# PGTN_daisy3_exp_32io.net
KiCad netlist of a schematic drawn in EAGLE
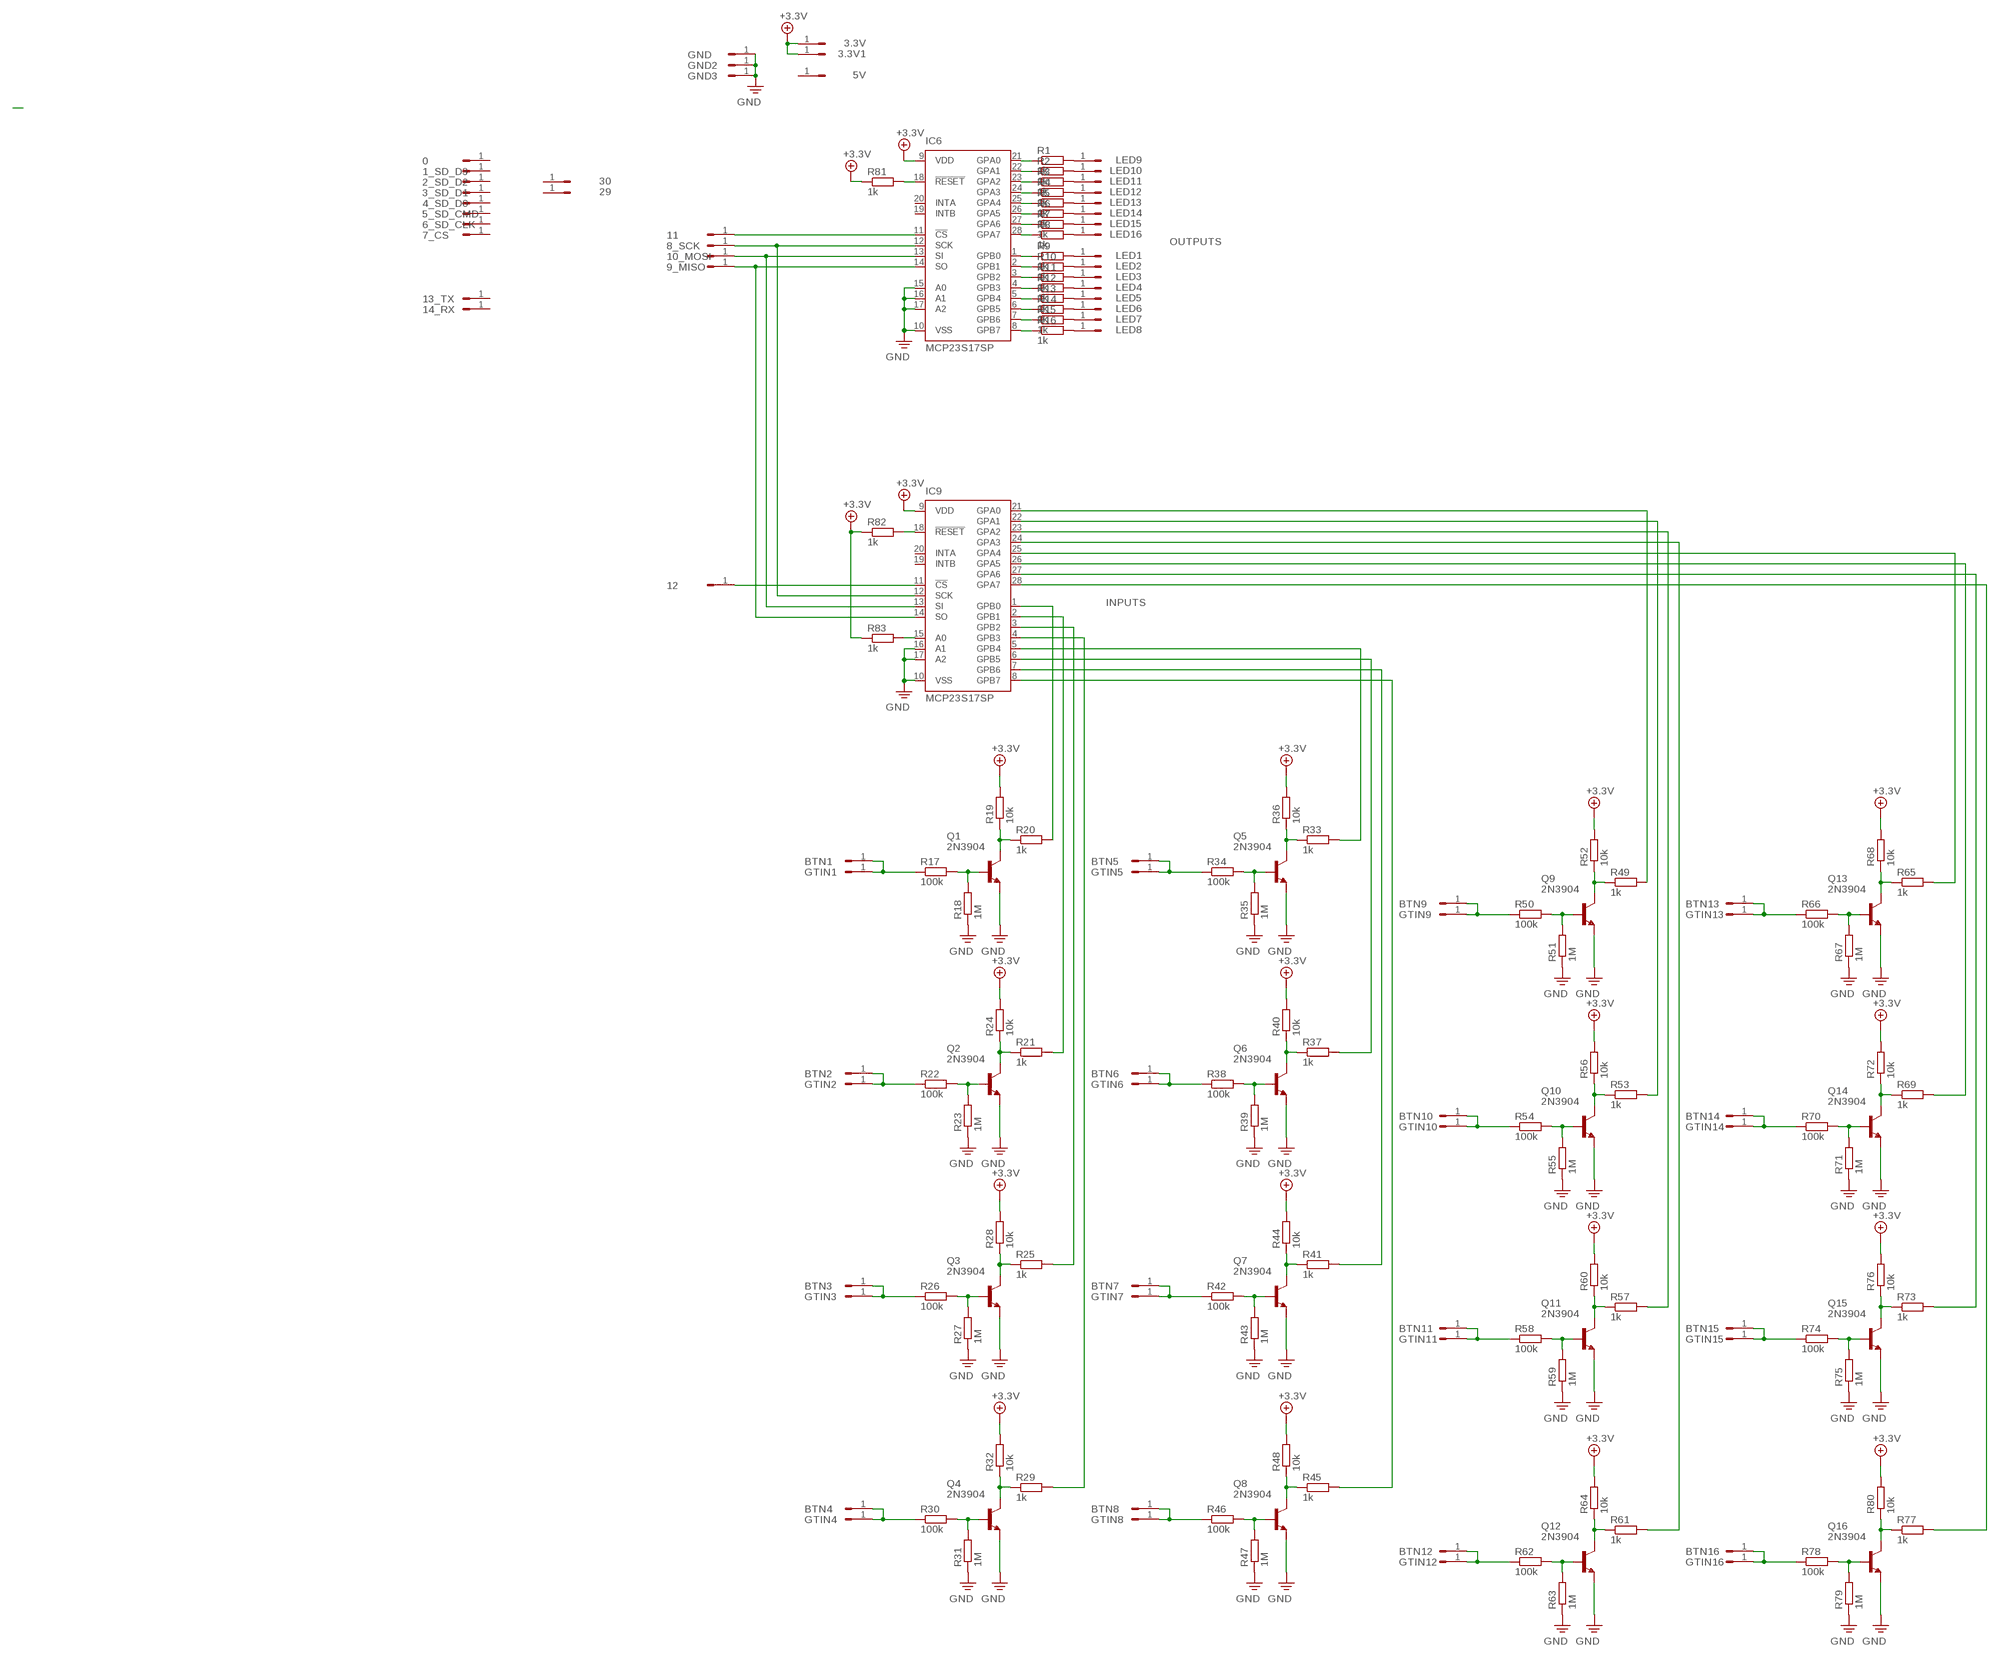
[diagram p0: schematic, sheet 1]

(export (version "E")
  (design (tool "Eeschema 10.0.6"))
  (components
    (comp (ref "0")
      (value "HEADER/MALE/01")
      (footprint "eagle-import:HEADER_MALE_01")
      (fields (field (name "SPICEPREFIX") "X"))
      (libsource (lib "eagle-import") (part "HEADER/MALE/01"))
    )
    (comp (ref "1_SD_D3")
      (value "HEADER/MALE/01")
      (footprint "eagle-import:HEADER_MALE_01")
      (fields (field (name "SPICEPREFIX") "X"))
      (libsource (lib "eagle-import") (part "HEADER/MALE/01"))
    )
    (comp (ref "2_SD_D2")
      (value "HEADER/MALE/01")
      (footprint "eagle-import:HEADER_MALE_01")
      (fields (field (name "SPICEPREFIX") "X"))
      (libsource (lib "eagle-import") (part "HEADER/MALE/01"))
    )
    (comp (ref "3.3V")
      (value "HEADER/MALE/01")
      (footprint "eagle-import:HEADER_MALE_01")
      (fields (field (name "SPICEPREFIX") "X"))
      (libsource (lib "eagle-import") (part "HEADER/MALE/01"))
    )
    (comp (ref "3.3V1")
      (value "HEADER/MALE/01")
      (footprint "eagle-import:HEADER_MALE_01")
      (fields (field (name "SPICEPREFIX") "X"))
      (libsource (lib "eagle-import") (part "HEADER/MALE/01"))
    )
    (comp (ref "3_SD_D1")
      (value "HEADER/MALE/01")
      (footprint "eagle-import:HEADER_MALE_01")
      (fields (field (name "SPICEPREFIX") "X"))
      (libsource (lib "eagle-import") (part "HEADER/MALE/01"))
    )
    (comp (ref "4_SD_D0")
      (value "HEADER/MALE/01")
      (footprint "eagle-import:HEADER_MALE_01")
      (fields (field (name "SPICEPREFIX") "X"))
      (libsource (lib "eagle-import") (part "HEADER/MALE/01"))
    )
    (comp (ref "5V")
      (value "HEADER/MALE/01")
      (footprint "eagle-import:HEADER_MALE_01")
      (fields (field (name "SPICEPREFIX") "X"))
      (libsource (lib "eagle-import") (part "HEADER/MALE/01"))
    )
    (comp (ref "5_SD_CMD")
      (value "HEADER/MALE/01")
      (footprint "eagle-import:HEADER_MALE_01")
      (fields (field (name "SPICEPREFIX") "X"))
      (libsource (lib "eagle-import") (part "HEADER/MALE/01"))
    )
    (comp (ref "6_SD_CLK")
      (value "HEADER/MALE/01")
      (footprint "eagle-import:HEADER_MALE_01")
      (fields (field (name "SPICEPREFIX") "X"))
      (libsource (lib "eagle-import") (part "HEADER/MALE/01"))
    )
    (comp (ref "7_CS")
      (value "HEADER/MALE/01")
      (footprint "eagle-import:HEADER_MALE_01")
      (fields (field (name "SPICEPREFIX") "X"))
      (libsource (lib "eagle-import") (part "HEADER/MALE/01"))
    )
    (comp (ref "8_SCK")
      (value "HEADER/MALE/01")
      (footprint "eagle-import:HEADER_MALE_01")
      (fields (field (name "SPICEPREFIX") "X"))
      (libsource (lib "eagle-import") (part "HEADER/MALE/01"))
    )
    (comp (ref "9_MISO")
      (value "HEADER/MALE/01")
      (footprint "eagle-import:HEADER_MALE_01")
      (fields (field (name "SPICEPREFIX") "X"))
      (libsource (lib "eagle-import") (part "HEADER/MALE/01"))
    )
    (comp (ref "10_MOSI")
      (value "HEADER/MALE/01")
      (footprint "eagle-import:HEADER_MALE_01")
      (fields (field (name "SPICEPREFIX") "X"))
      (libsource (lib "eagle-import") (part "HEADER/MALE/01"))
    )
    (comp (ref "11")
      (value "HEADER/MALE/01")
      (footprint "eagle-import:HEADER_MALE_01")
      (fields (field (name "SPICEPREFIX") "X"))
      (libsource (lib "eagle-import") (part "HEADER/MALE/01"))
    )
    (comp (ref "12")
      (value "HEADER/MALE/01")
      (footprint "eagle-import:HEADER_MALE_01")
      (fields (field (name "SPICEPREFIX") "X"))
      (libsource (lib "eagle-import") (part "HEADER/MALE/01"))
    )
    (comp (ref "13_TX")
      (value "HEADER/MALE/01")
      (footprint "eagle-import:HEADER_MALE_01")
      (fields (field (name "SPICEPREFIX") "X"))
      (libsource (lib "eagle-import") (part "HEADER/MALE/01"))
    )
    (comp (ref "14_RX")
      (value "HEADER/MALE/01")
      (footprint "eagle-import:HEADER_MALE_01")
      (fields (field (name "SPICEPREFIX") "X"))
      (libsource (lib "eagle-import") (part "HEADER/MALE/01"))
    )
    (comp (ref "29")
      (value "HEADER/MALE/01")
      (footprint "eagle-import:HEADER_MALE_01")
      (fields (field (name "SPICEPREFIX") "X"))
      (libsource (lib "eagle-import") (part "HEADER/MALE/01"))
    )
    (comp (ref "30")
      (value "HEADER/MALE/01")
      (footprint "eagle-import:HEADER_MALE_01")
      (fields (field (name "SPICEPREFIX") "X"))
      (libsource (lib "eagle-import") (part "HEADER/MALE/01"))
    )
    (comp (ref "BTN1")
      (value "HEADER/MALE/01")
      (footprint "eagle-import:HEADER_MALE_01")
      (fields (field (name "SPICEPREFIX") "X"))
      (libsource (lib "eagle-import") (part "HEADER/MALE/01"))
    )
    (comp (ref "BTN2")
      (value "HEADER/MALE/01")
      (footprint "eagle-import:HEADER_MALE_01")
      (fields (field (name "SPICEPREFIX") "X"))
      (libsource (lib "eagle-import") (part "HEADER/MALE/01"))
    )
    (comp (ref "BTN3")
      (value "HEADER/MALE/01")
      (footprint "eagle-import:HEADER_MALE_01")
      (fields (field (name "SPICEPREFIX") "X"))
      (libsource (lib "eagle-import") (part "HEADER/MALE/01"))
    )
    (comp (ref "BTN4")
      (value "HEADER/MALE/01")
      (footprint "eagle-import:HEADER_MALE_01")
      (fields (field (name "SPICEPREFIX") "X"))
      (libsource (lib "eagle-import") (part "HEADER/MALE/01"))
    )
    (comp (ref "BTN5")
      (value "HEADER/MALE/01")
      (footprint "eagle-import:HEADER_MALE_01")
      (fields (field (name "SPICEPREFIX") "X"))
      (libsource (lib "eagle-import") (part "HEADER/MALE/01"))
    )
    (comp (ref "BTN6")
      (value "HEADER/MALE/01")
      (footprint "eagle-import:HEADER_MALE_01")
      (fields (field (name "SPICEPREFIX") "X"))
      (libsource (lib "eagle-import") (part "HEADER/MALE/01"))
    )
    (comp (ref "BTN7")
      (value "HEADER/MALE/01")
      (footprint "eagle-import:HEADER_MALE_01")
      (fields (field (name "SPICEPREFIX") "X"))
      (libsource (lib "eagle-import") (part "HEADER/MALE/01"))
    )
    (comp (ref "BTN8")
      (value "HEADER/MALE/01")
      (footprint "eagle-import:HEADER_MALE_01")
      (fields (field (name "SPICEPREFIX") "X"))
      (libsource (lib "eagle-import") (part "HEADER/MALE/01"))
    )
    (comp (ref "BTN9")
      (value "HEADER/MALE/01")
      (footprint "eagle-import:HEADER_MALE_01")
      (fields (field (name "SPICEPREFIX") "X"))
      (libsource (lib "eagle-import") (part "HEADER/MALE/01"))
    )
    (comp (ref "BTN10")
      (value "HEADER/MALE/01")
      (footprint "eagle-import:HEADER_MALE_01")
      (fields (field (name "SPICEPREFIX") "X"))
      (libsource (lib "eagle-import") (part "HEADER/MALE/01"))
    )
    (comp (ref "BTN11")
      (value "HEADER/MALE/01")
      (footprint "eagle-import:HEADER_MALE_01")
      (fields (field (name "SPICEPREFIX") "X"))
      (libsource (lib "eagle-import") (part "HEADER/MALE/01"))
    )
    (comp (ref "BTN12")
      (value "HEADER/MALE/01")
      (footprint "eagle-import:HEADER_MALE_01")
      (fields (field (name "SPICEPREFIX") "X"))
      (libsource (lib "eagle-import") (part "HEADER/MALE/01"))
    )
    (comp (ref "BTN13")
      (value "HEADER/MALE/01")
      (footprint "eagle-import:HEADER_MALE_01")
      (fields (field (name "SPICEPREFIX") "X"))
      (libsource (lib "eagle-import") (part "HEADER/MALE/01"))
    )
    (comp (ref "BTN14")
      (value "HEADER/MALE/01")
      (footprint "eagle-import:HEADER_MALE_01")
      (fields (field (name "SPICEPREFIX") "X"))
      (libsource (lib "eagle-import") (part "HEADER/MALE/01"))
    )
    (comp (ref "BTN15")
      (value "HEADER/MALE/01")
      (footprint "eagle-import:HEADER_MALE_01")
      (fields (field (name "SPICEPREFIX") "X"))
      (libsource (lib "eagle-import") (part "HEADER/MALE/01"))
    )
    (comp (ref "BTN16")
      (value "HEADER/MALE/01")
      (footprint "eagle-import:HEADER_MALE_01")
      (fields (field (name "SPICEPREFIX") "X"))
      (libsource (lib "eagle-import") (part "HEADER/MALE/01"))
    )
    (comp (ref "GND")
      (value "HEADER/MALE/01")
      (footprint "eagle-import:HEADER_MALE_01")
      (fields (field (name "SPICEPREFIX") "X"))
      (libsource (lib "eagle-import") (part "HEADER/MALE/01"))
    )
    (comp (ref "GND2")
      (value "HEADER/MALE/01")
      (footprint "eagle-import:HEADER_MALE_01")
      (fields (field (name "SPICEPREFIX") "X"))
      (libsource (lib "eagle-import") (part "HEADER/MALE/01"))
    )
    (comp (ref "GND3")
      (value "HEADER/MALE/01")
      (footprint "eagle-import:HEADER_MALE_01")
      (fields (field (name "SPICEPREFIX") "X"))
      (libsource (lib "eagle-import") (part "HEADER/MALE/01"))
    )
    (comp (ref "GTIN1")
      (value "HEADER/MALE/01")
      (footprint "eagle-import:HEADER_MALE_01")
      (fields (field (name "SPICEPREFIX") "X"))
      (libsource (lib "eagle-import") (part "HEADER/MALE/01"))
    )
    (comp (ref "GTIN2")
      (value "HEADER/MALE/01")
      (footprint "eagle-import:HEADER_MALE_01")
      (fields (field (name "SPICEPREFIX") "X"))
      (libsource (lib "eagle-import") (part "HEADER/MALE/01"))
    )
    (comp (ref "GTIN3")
      (value "HEADER/MALE/01")
      (footprint "eagle-import:HEADER_MALE_01")
      (fields (field (name "SPICEPREFIX") "X"))
      (libsource (lib "eagle-import") (part "HEADER/MALE/01"))
    )
    (comp (ref "GTIN4")
      (value "HEADER/MALE/01")
      (footprint "eagle-import:HEADER_MALE_01")
      (fields (field (name "SPICEPREFIX") "X"))
      (libsource (lib "eagle-import") (part "HEADER/MALE/01"))
    )
    (comp (ref "GTIN5")
      (value "HEADER/MALE/01")
      (footprint "eagle-import:HEADER_MALE_01")
      (fields (field (name "SPICEPREFIX") "X"))
      (libsource (lib "eagle-import") (part "HEADER/MALE/01"))
    )
    (comp (ref "GTIN6")
      (value "HEADER/MALE/01")
      (footprint "eagle-import:HEADER_MALE_01")
      (fields (field (name "SPICEPREFIX") "X"))
      (libsource (lib "eagle-import") (part "HEADER/MALE/01"))
    )
    (comp (ref "GTIN7")
      (value "HEADER/MALE/01")
      (footprint "eagle-import:HEADER_MALE_01")
      (fields (field (name "SPICEPREFIX") "X"))
      (libsource (lib "eagle-import") (part "HEADER/MALE/01"))
    )
    (comp (ref "GTIN8")
      (value "HEADER/MALE/01")
      (footprint "eagle-import:HEADER_MALE_01")
      (fields (field (name "SPICEPREFIX") "X"))
      (libsource (lib "eagle-import") (part "HEADER/MALE/01"))
    )
    (comp (ref "GTIN9")
      (value "HEADER/MALE/01")
      (footprint "eagle-import:HEADER_MALE_01")
      (fields (field (name "SPICEPREFIX") "X"))
      (libsource (lib "eagle-import") (part "HEADER/MALE/01"))
    )
    (comp (ref "GTIN10")
      (value "HEADER/MALE/01")
      (footprint "eagle-import:HEADER_MALE_01")
      (fields (field (name "SPICEPREFIX") "X"))
      (libsource (lib "eagle-import") (part "HEADER/MALE/01"))
    )
    (comp (ref "GTIN11")
      (value "HEADER/MALE/01")
      (footprint "eagle-import:HEADER_MALE_01")
      (fields (field (name "SPICEPREFIX") "X"))
      (libsource (lib "eagle-import") (part "HEADER/MALE/01"))
    )
    (comp (ref "GTIN12")
      (value "HEADER/MALE/01")
      (footprint "eagle-import:HEADER_MALE_01")
      (fields (field (name "SPICEPREFIX") "X"))
      (libsource (lib "eagle-import") (part "HEADER/MALE/01"))
    )
    (comp (ref "GTIN13")
      (value "HEADER/MALE/01")
      (footprint "eagle-import:HEADER_MALE_01")
      (fields (field (name "SPICEPREFIX") "X"))
      (libsource (lib "eagle-import") (part "HEADER/MALE/01"))
    )
    (comp (ref "GTIN14")
      (value "HEADER/MALE/01")
      (footprint "eagle-import:HEADER_MALE_01")
      (fields (field (name "SPICEPREFIX") "X"))
      (libsource (lib "eagle-import") (part "HEADER/MALE/01"))
    )
    (comp (ref "GTIN15")
      (value "HEADER/MALE/01")
      (footprint "eagle-import:HEADER_MALE_01")
      (fields (field (name "SPICEPREFIX") "X"))
      (libsource (lib "eagle-import") (part "HEADER/MALE/01"))
    )
    (comp (ref "GTIN16")
      (value "HEADER/MALE/01")
      (footprint "eagle-import:HEADER_MALE_01")
      (fields (field (name "SPICEPREFIX") "X"))
      (libsource (lib "eagle-import") (part "HEADER/MALE/01"))
    )
    (comp (ref "IC6")
      (value "MCP23S17SP")
      (footprint "eagle-import:DIL28-3")
      (fields (field (name "MF") "MICROCHIP") (field (name "MPN") "MCP23S17-E/SP"))
      (libsource (lib "eagle-import") (part "MCP23S17SP"))
    )
    (comp (ref "IC9")
      (value "MCP23S17SP")
      (footprint "eagle-import:DIL28-3")
      (fields (field (name "MF") "MICROCHIP") (field (name "MPN") "MCP23S17-E/SP"))
      (libsource (lib "eagle-import") (part "MCP23S17SP"))
    )
    (comp (ref "LED1")
      (value "HEADER/MALE/01")
      (footprint "eagle-import:HEADER_MALE_01")
      (fields (field (name "SPICEPREFIX") "X"))
      (libsource (lib "eagle-import") (part "HEADER/MALE/01"))
    )
    (comp (ref "LED2")
      (value "HEADER/MALE/01")
      (footprint "eagle-import:HEADER_MALE_01")
      (fields (field (name "SPICEPREFIX") "X"))
      (libsource (lib "eagle-import") (part "HEADER/MALE/01"))
    )
    (comp (ref "LED3")
      (value "HEADER/MALE/01")
      (footprint "eagle-import:HEADER_MALE_01")
      (fields (field (name "SPICEPREFIX") "X"))
      (libsource (lib "eagle-import") (part "HEADER/MALE/01"))
    )
    (comp (ref "LED4")
      (value "HEADER/MALE/01")
      (footprint "eagle-import:HEADER_MALE_01")
      (fields (field (name "SPICEPREFIX") "X"))
      (libsource (lib "eagle-import") (part "HEADER/MALE/01"))
    )
    (comp (ref "LED5")
      (value "HEADER/MALE/01")
      (footprint "eagle-import:HEADER_MALE_01")
      (fields (field (name "SPICEPREFIX") "X"))
      (libsource (lib "eagle-import") (part "HEADER/MALE/01"))
    )
    (comp (ref "LED6")
      (value "HEADER/MALE/01")
      (footprint "eagle-import:HEADER_MALE_01")
      (fields (field (name "SPICEPREFIX") "X"))
      (libsource (lib "eagle-import") (part "HEADER/MALE/01"))
    )
    (comp (ref "LED7")
      (value "HEADER/MALE/01")
      (footprint "eagle-import:HEADER_MALE_01")
      (fields (field (name "SPICEPREFIX") "X"))
      (libsource (lib "eagle-import") (part "HEADER/MALE/01"))
    )
    (comp (ref "LED8")
      (value "HEADER/MALE/01")
      (footprint "eagle-import:HEADER_MALE_01")
      (fields (field (name "SPICEPREFIX") "X"))
      (libsource (lib "eagle-import") (part "HEADER/MALE/01"))
    )
    (comp (ref "LED9")
      (value "HEADER/MALE/01")
      (footprint "eagle-import:HEADER_MALE_01")
      (fields (field (name "SPICEPREFIX") "X"))
      (libsource (lib "eagle-import") (part "HEADER/MALE/01"))
    )
    (comp (ref "LED10")
      (value "HEADER/MALE/01")
      (footprint "eagle-import:HEADER_MALE_01")
      (fields (field (name "SPICEPREFIX") "X"))
      (libsource (lib "eagle-import") (part "HEADER/MALE/01"))
    )
    (comp (ref "LED11")
      (value "HEADER/MALE/01")
      (footprint "eagle-import:HEADER_MALE_01")
      (fields (field (name "SPICEPREFIX") "X"))
      (libsource (lib "eagle-import") (part "HEADER/MALE/01"))
    )
    (comp (ref "LED12")
      (value "HEADER/MALE/01")
      (footprint "eagle-import:HEADER_MALE_01")
      (fields (field (name "SPICEPREFIX") "X"))
      (libsource (lib "eagle-import") (part "HEADER/MALE/01"))
    )
    (comp (ref "LED13")
      (value "HEADER/MALE/01")
      (footprint "eagle-import:HEADER_MALE_01")
      (fields (field (name "SPICEPREFIX") "X"))
      (libsource (lib "eagle-import") (part "HEADER/MALE/01"))
    )
    (comp (ref "LED14")
      (value "HEADER/MALE/01")
      (footprint "eagle-import:HEADER_MALE_01")
      (fields (field (name "SPICEPREFIX") "X"))
      (libsource (lib "eagle-import") (part "HEADER/MALE/01"))
    )
    (comp (ref "LED15")
      (value "HEADER/MALE/01")
      (footprint "eagle-import:HEADER_MALE_01")
      (fields (field (name "SPICEPREFIX") "X"))
      (libsource (lib "eagle-import") (part "HEADER/MALE/01"))
    )
    (comp (ref "LED16")
      (value "HEADER/MALE/01")
      (footprint "eagle-import:HEADER_MALE_01")
      (fields (field (name "SPICEPREFIX") "X"))
      (libsource (lib "eagle-import") (part "HEADER/MALE/01"))
    )
    (comp (ref "Q1")
      (value "2N3904")
      (footprint "eagle-import:TO92")
      (libsource (lib "eagle-import") (part "2N3904"))
    )
    (comp (ref "Q2")
      (value "2N3904")
      (footprint "eagle-import:TO92")
      (libsource (lib "eagle-import") (part "2N3904"))
    )
    (comp (ref "Q3")
      (value "2N3904")
      (footprint "eagle-import:TO92")
      (libsource (lib "eagle-import") (part "2N3904"))
    )
    (comp (ref "Q4")
      (value "2N3904")
      (footprint "eagle-import:TO92")
      (libsource (lib "eagle-import") (part "2N3904"))
    )
    (comp (ref "Q5")
      (value "2N3904")
      (footprint "eagle-import:TO92")
      (libsource (lib "eagle-import") (part "2N3904"))
    )
    (comp (ref "Q6")
      (value "2N3904")
      (footprint "eagle-import:TO92")
      (libsource (lib "eagle-import") (part "2N3904"))
    )
    (comp (ref "Q7")
      (value "2N3904")
      (footprint "eagle-import:TO92")
      (libsource (lib "eagle-import") (part "2N3904"))
    )
    (comp (ref "Q8")
      (value "2N3904")
      (footprint "eagle-import:TO92")
      (libsource (lib "eagle-import") (part "2N3904"))
    )
    (comp (ref "Q9")
      (value "2N3904")
      (footprint "eagle-import:TO92")
      (libsource (lib "eagle-import") (part "2N3904"))
    )
    (comp (ref "Q10")
      (value "2N3904")
      (footprint "eagle-import:TO92")
      (libsource (lib "eagle-import") (part "2N3904"))
    )
    (comp (ref "Q11")
      (value "2N3904")
      (footprint "eagle-import:TO92")
      (libsource (lib "eagle-import") (part "2N3904"))
    )
    (comp (ref "Q12")
      (value "2N3904")
      (footprint "eagle-import:TO92")
      (libsource (lib "eagle-import") (part "2N3904"))
    )
    (comp (ref "Q13")
      (value "2N3904")
      (footprint "eagle-import:TO92")
      (libsource (lib "eagle-import") (part "2N3904"))
    )
    (comp (ref "Q14")
      (value "2N3904")
      (footprint "eagle-import:TO92")
      (libsource (lib "eagle-import") (part "2N3904"))
    )
    (comp (ref "Q15")
      (value "2N3904")
      (footprint "eagle-import:TO92")
      (libsource (lib "eagle-import") (part "2N3904"))
    )
    (comp (ref "Q16")
      (value "2N3904")
      (footprint "eagle-import:TO92")
      (libsource (lib "eagle-import") (part "2N3904"))
    )
    (comp (ref "R1")
      (value "1k")
      (footprint "eagle-import:RESISTOR_7.5")
      (libsource (lib "eagle-import") (part "RESISTORRESISTOR/UPRIGHT/7.5"))
    )
    (comp (ref "R2")
      (value "1k")
      (footprint "eagle-import:RESISTOR_7.5")
      (libsource (lib "eagle-import") (part "RESISTORRESISTOR/UPRIGHT/7.5"))
    )
    (comp (ref "R3")
      (value "1k")
      (footprint "eagle-import:RESISTOR_7.5")
      (libsource (lib "eagle-import") (part "RESISTORRESISTOR/UPRIGHT/7.5"))
    )
    (comp (ref "R4")
      (value "1k")
      (footprint "eagle-import:RESISTOR_7.5")
      (libsource (lib "eagle-import") (part "RESISTORRESISTOR/UPRIGHT/7.5"))
    )
    (comp (ref "R5")
      (value "1k")
      (footprint "eagle-import:RESISTOR_7.5")
      (libsource (lib "eagle-import") (part "RESISTORRESISTOR/UPRIGHT/7.5"))
    )
    (comp (ref "R6")
      (value "1k")
      (footprint "eagle-import:RESISTOR_7.5")
      (libsource (lib "eagle-import") (part "RESISTORRESISTOR/UPRIGHT/7.5"))
    )
    (comp (ref "R7")
      (value "1k")
      (footprint "eagle-import:RESISTOR_7.5")
      (libsource (lib "eagle-import") (part "RESISTORRESISTOR/UPRIGHT/7.5"))
    )
    (comp (ref "R8")
      (value "1k")
      (footprint "eagle-import:RESISTOR_7.5")
      (libsource (lib "eagle-import") (part "RESISTORRESISTOR/UPRIGHT/7.5"))
    )
    (comp (ref "R9")
      (value "1k")
      (footprint "eagle-import:RESISTOR_7.5")
      (libsource (lib "eagle-import") (part "RESISTORRESISTOR/UPRIGHT/7.5"))
    )
    (comp (ref "R10")
      (value "1k")
      (footprint "eagle-import:RESISTOR_7.5")
      (libsource (lib "eagle-import") (part "RESISTORRESISTOR/UPRIGHT/7.5"))
    )
    (comp (ref "R11")
      (value "1k")
      (footprint "eagle-import:RESISTOR_7.5")
      (libsource (lib "eagle-import") (part "RESISTORRESISTOR/UPRIGHT/7.5"))
    )
    (comp (ref "R12")
      (value "1k")
      (footprint "eagle-import:RESISTOR_7.5")
      (libsource (lib "eagle-import") (part "RESISTORRESISTOR/UPRIGHT/7.5"))
    )
    (comp (ref "R13")
      (value "1k")
      (footprint "eagle-import:RESISTOR_7.5")
      (libsource (lib "eagle-import") (part "RESISTORRESISTOR/UPRIGHT/7.5"))
    )
    (comp (ref "R14")
      (value "1k")
      (footprint "eagle-import:RESISTOR_7.5")
      (libsource (lib "eagle-import") (part "RESISTORRESISTOR/UPRIGHT/7.5"))
    )
    (comp (ref "R15")
      (value "1k")
      (footprint "eagle-import:RESISTOR_7.5")
      (libsource (lib "eagle-import") (part "RESISTORRESISTOR/UPRIGHT/7.5"))
    )
    (comp (ref "R16")
      (value "1k")
      (footprint "eagle-import:RESISTOR_7.5")
      (libsource (lib "eagle-import") (part "RESISTORRESISTOR/UPRIGHT/7.5"))
    )
    (comp (ref "R17")
      (value "100k")
      (footprint "eagle-import:RESISTOR_7.5")
      (libsource (lib "eagle-import") (part "RESISTORRESISTOR/UPRIGHT/7.5"))
    )
    (comp (ref "R18")
      (value "1M")
      (footprint "eagle-import:RESISTOR_7.5")
      (libsource (lib "eagle-import") (part "RESISTORRESISTOR/UPRIGHT/7.5"))
    )
    (comp (ref "R19")
      (value "10k")
      (footprint "eagle-import:RESISTOR_7.5")
      (libsource (lib "eagle-import") (part "RESISTORRESISTOR/UPRIGHT/7.5"))
    )
    (comp (ref "R20")
      (value "1k")
      (footprint "eagle-import:RESISTOR_7.5")
      (libsource (lib "eagle-import") (part "RESISTORRESISTOR/UPRIGHT/7.5"))
    )
    (comp (ref "R21")
      (value "1k")
      (footprint "eagle-import:RESISTOR_7.5")
      (libsource (lib "eagle-import") (part "RESISTORRESISTOR/UPRIGHT/7.5"))
    )
    (comp (ref "R22")
      (value "100k")
      (footprint "eagle-import:RESISTOR_7.5")
      (libsource (lib "eagle-import") (part "RESISTORRESISTOR/UPRIGHT/7.5"))
    )
    (comp (ref "R23")
      (value "1M")
      (footprint "eagle-import:RESISTOR_7.5")
      (libsource (lib "eagle-import") (part "RESISTORRESISTOR/UPRIGHT/7.5"))
    )
    (comp (ref "R24")
      (value "10k")
      (footprint "eagle-import:RESISTOR_7.5")
      (libsource (lib "eagle-import") (part "RESISTORRESISTOR/UPRIGHT/7.5"))
    )
    (comp (ref "R25")
      (value "1k")
      (footprint "eagle-import:RESISTOR_7.5")
      (libsource (lib "eagle-import") (part "RESISTORRESISTOR/UPRIGHT/7.5"))
    )
    (comp (ref "R26")
      (value "100k")
      (footprint "eagle-import:RESISTOR_7.5")
      (libsource (lib "eagle-import") (part "RESISTORRESISTOR/UPRIGHT/7.5"))
    )
    (comp (ref "R27")
      (value "1M")
      (footprint "eagle-import:RESISTOR_7.5")
      (libsource (lib "eagle-import") (part "RESISTORRESISTOR/UPRIGHT/7.5"))
    )
    (comp (ref "R28")
      (value "10k")
      (footprint "eagle-import:RESISTOR_7.5")
      (libsource (lib "eagle-import") (part "RESISTORRESISTOR/UPRIGHT/7.5"))
    )
    (comp (ref "R29")
      (value "1k")
      (footprint "eagle-import:RESISTOR_7.5")
      (libsource (lib "eagle-import") (part "RESISTORRESISTOR/UPRIGHT/7.5"))
    )
    (comp (ref "R30")
      (value "100k")
      (footprint "eagle-import:RESISTOR_7.5")
      (libsource (lib "eagle-import") (part "RESISTORRESISTOR/UPRIGHT/7.5"))
    )
    (comp (ref "R31")
      (value "1M")
      (footprint "eagle-import:RESISTOR_7.5")
      (libsource (lib "eagle-import") (part "RESISTORRESISTOR/UPRIGHT/7.5"))
    )
    (comp (ref "R32")
      (value "10k")
      (footprint "eagle-import:RESISTOR_7.5")
      (libsource (lib "eagle-import") (part "RESISTORRESISTOR/UPRIGHT/7.5"))
    )
    (comp (ref "R33")
      (value "1k")
      (footprint "eagle-import:RESISTOR_7.5")
      (libsource (lib "eagle-import") (part "RESISTORRESISTOR/UPRIGHT/7.5"))
    )
    (comp (ref "R34")
      (value "100k")
      (footprint "eagle-import:RESISTOR_7.5")
      (libsource (lib "eagle-import") (part "RESISTORRESISTOR/UPRIGHT/7.5"))
    )
    (comp (ref "R35")
      (value "1M")
      (footprint "eagle-import:RESISTOR_7.5")
      (libsource (lib "eagle-import") (part "RESISTORRESISTOR/UPRIGHT/7.5"))
    )
    (comp (ref "R36")
      (value "10k")
      (footprint "eagle-import:RESISTOR_7.5")
      (libsource (lib "eagle-import") (part "RESISTORRESISTOR/UPRIGHT/7.5"))
    )
    (comp (ref "R37")
      (value "1k")
      (footprint "eagle-import:RESISTOR_7.5")
      (libsource (lib "eagle-import") (part "RESISTORRESISTOR/UPRIGHT/7.5"))
    )
    (comp (ref "R38")
      (value "100k")
      (footprint "eagle-import:RESISTOR_7.5")
      (libsource (lib "eagle-import") (part "RESISTORRESISTOR/UPRIGHT/7.5"))
    )
    (comp (ref "R39")
      (value "1M")
      (footprint "eagle-import:RESISTOR_7.5")
      (libsource (lib "eagle-import") (part "RESISTORRESISTOR/UPRIGHT/7.5"))
    )
    (comp (ref "R40")
      (value "10k")
      (footprint "eagle-import:RESISTOR_7.5")
      (libsource (lib "eagle-import") (part "RESISTORRESISTOR/UPRIGHT/7.5"))
    )
    (comp (ref "R41")
      (value "1k")
      (footprint "eagle-import:RESISTOR_7.5")
      (libsource (lib "eagle-import") (part "RESISTORRESISTOR/UPRIGHT/7.5"))
    )
    (comp (ref "R42")
      (value "100k")
      (footprint "eagle-import:RESISTOR_7.5")
      (libsource (lib "eagle-import") (part "RESISTORRESISTOR/UPRIGHT/7.5"))
    )
    (comp (ref "R43")
      (value "1M")
      (footprint "eagle-import:RESISTOR_7.5")
      (libsource (lib "eagle-import") (part "RESISTORRESISTOR/UPRIGHT/7.5"))
    )
    (comp (ref "R44")
      (value "10k")
      (footprint "eagle-import:RESISTOR_7.5")
      (libsource (lib "eagle-import") (part "RESISTORRESISTOR/UPRIGHT/7.5"))
    )
    (comp (ref "R45")
      (value "1k")
      (footprint "eagle-import:RESISTOR_7.5")
      (libsource (lib "eagle-import") (part "RESISTORRESISTOR/UPRIGHT/7.5"))
    )
    (comp (ref "R46")
      (value "100k")
      (footprint "eagle-import:RESISTOR_7.5")
      (libsource (lib "eagle-import") (part "RESISTORRESISTOR/UPRIGHT/7.5"))
    )
    (comp (ref "R47")
      (value "1M")
      (footprint "eagle-import:RESISTOR_7.5")
      (libsource (lib "eagle-import") (part "RESISTORRESISTOR/UPRIGHT/7.5"))
    )
    (comp (ref "R48")
      (value "10k")
      (footprint "eagle-import:RESISTOR_7.5")
      (libsource (lib "eagle-import") (part "RESISTORRESISTOR/UPRIGHT/7.5"))
    )
    (comp (ref "R49")
      (value "1k")
      (footprint "eagle-import:RESISTOR_7.5")
      (libsource (lib "eagle-import") (part "RESISTORRESISTOR/UPRIGHT/7.5"))
    )
    (comp (ref "R50")
      (value "100k")
      (footprint "eagle-import:RESISTOR_7.5")
      (libsource (lib "eagle-import") (part "RESISTORRESISTOR/UPRIGHT/7.5"))
    )
    (comp (ref "R51")
      (value "1M")
      (footprint "eagle-import:RESISTOR_7.5")
      (libsource (lib "eagle-import") (part "RESISTORRESISTOR/UPRIGHT/7.5"))
    )
    (comp (ref "R52")
      (value "10k")
      (footprint "eagle-import:RESISTOR_7.5")
      (libsource (lib "eagle-import") (part "RESISTORRESISTOR/UPRIGHT/7.5"))
    )
    (comp (ref "R53")
      (value "1k")
      (footprint "eagle-import:RESISTOR_7.5")
      (libsource (lib "eagle-import") (part "RESISTORRESISTOR/UPRIGHT/7.5"))
    )
    (comp (ref "R54")
      (value "100k")
      (footprint "eagle-import:RESISTOR_7.5")
      (libsource (lib "eagle-import") (part "RESISTORRESISTOR/UPRIGHT/7.5"))
    )
    (comp (ref "R55")
      (value "1M")
      (footprint "eagle-import:RESISTOR_7.5")
      (libsource (lib "eagle-import") (part "RESISTORRESISTOR/UPRIGHT/7.5"))
    )
    (comp (ref "R56")
      (value "10k")
      (footprint "eagle-import:RESISTOR_7.5")
      (libsource (lib "eagle-import") (part "RESISTORRESISTOR/UPRIGHT/7.5"))
    )
    (comp (ref "R57")
      (value "1k")
      (footprint "eagle-import:RESISTOR_7.5")
      (libsource (lib "eagle-import") (part "RESISTORRESISTOR/UPRIGHT/7.5"))
    )
    (comp (ref "R58")
      (value "100k")
      (footprint "eagle-import:RESISTOR_7.5")
      (libsource (lib "eagle-import") (part "RESISTORRESISTOR/UPRIGHT/7.5"))
    )
    (comp (ref "R59")
      (value "1M")
      (footprint "eagle-import:RESISTOR_7.5")
      (libsource (lib "eagle-import") (part "RESISTORRESISTOR/UPRIGHT/7.5"))
    )
    (comp (ref "R60")
      (value "10k")
      (footprint "eagle-import:RESISTOR_7.5")
      (libsource (lib "eagle-import") (part "RESISTORRESISTOR/UPRIGHT/7.5"))
    )
    (comp (ref "R61")
      (value "1k")
      (footprint "eagle-import:RESISTOR_7.5")
      (libsource (lib "eagle-import") (part "RESISTORRESISTOR/UPRIGHT/7.5"))
    )
    (comp (ref "R62")
      (value "100k")
      (footprint "eagle-import:RESISTOR_7.5")
      (libsource (lib "eagle-import") (part "RESISTORRESISTOR/UPRIGHT/7.5"))
    )
    (comp (ref "R63")
      (value "1M")
      (footprint "eagle-import:RESISTOR_7.5")
      (libsource (lib "eagle-import") (part "RESISTORRESISTOR/UPRIGHT/7.5"))
    )
    (comp (ref "R64")
      (value "10k")
      (footprint "eagle-import:RESISTOR_7.5")
      (libsource (lib "eagle-import") (part "RESISTORRESISTOR/UPRIGHT/7.5"))
    )
    (comp (ref "R65")
      (value "1k")
      (footprint "eagle-import:RESISTOR_7.5")
      (libsource (lib "eagle-import") (part "RESISTORRESISTOR/UPRIGHT/7.5"))
    )
    (comp (ref "R66")
      (value "100k")
      (footprint "eagle-import:RESISTOR_7.5")
      (libsource (lib "eagle-import") (part "RESISTORRESISTOR/UPRIGHT/7.5"))
    )
    (comp (ref "R67")
      (value "1M")
      (footprint "eagle-import:RESISTOR_7.5")
      (libsource (lib "eagle-import") (part "RESISTORRESISTOR/UPRIGHT/7.5"))
    )
    (comp (ref "R68")
      (value "10k")
      (footprint "eagle-import:RESISTOR_7.5")
      (libsource (lib "eagle-import") (part "RESISTORRESISTOR/UPRIGHT/7.5"))
    )
    (comp (ref "R69")
      (value "1k")
      (footprint "eagle-import:RESISTOR_7.5")
      (libsource (lib "eagle-import") (part "RESISTORRESISTOR/UPRIGHT/7.5"))
    )
    (comp (ref "R70")
      (value "100k")
      (footprint "eagle-import:RESISTOR_7.5")
      (libsource (lib "eagle-import") (part "RESISTORRESISTOR/UPRIGHT/7.5"))
    )
    (comp (ref "R71")
      (value "1M")
      (footprint "eagle-import:RESISTOR_7.5")
      (libsource (lib "eagle-import") (part "RESISTORRESISTOR/UPRIGHT/7.5"))
    )
    (comp (ref "R72")
      (value "10k")
      (footprint "eagle-import:RESISTOR_7.5")
      (libsource (lib "eagle-import") (part "RESISTORRESISTOR/UPRIGHT/7.5"))
    )
    (comp (ref "R73")
      (value "1k")
      (footprint "eagle-import:RESISTOR_7.5")
      (libsource (lib "eagle-import") (part "RESISTORRESISTOR/UPRIGHT/7.5"))
    )
    (comp (ref "R74")
      (value "100k")
      (footprint "eagle-import:RESISTOR_7.5")
      (libsource (lib "eagle-import") (part "RESISTORRESISTOR/UPRIGHT/7.5"))
    )
    (comp (ref "R75")
      (value "1M")
      (footprint "eagle-import:RESISTOR_7.5")
      (libsource (lib "eagle-import") (part "RESISTORRESISTOR/UPRIGHT/7.5"))
    )
    (comp (ref "R76")
      (value "10k")
      (footprint "eagle-import:RESISTOR_7.5")
      (libsource (lib "eagle-import") (part "RESISTORRESISTOR/UPRIGHT/7.5"))
    )
    (comp (ref "R77")
      (value "1k")
      (footprint "eagle-import:RESISTOR_7.5")
      (libsource (lib "eagle-import") (part "RESISTORRESISTOR/UPRIGHT/7.5"))
    )
    (comp (ref "R78")
      (value "100k")
      (footprint "eagle-import:RESISTOR_7.5")
      (libsource (lib "eagle-import") (part "RESISTORRESISTOR/UPRIGHT/7.5"))
    )
    (comp (ref "R79")
      (value "1M")
      (footprint "eagle-import:RESISTOR_7.5")
      (libsource (lib "eagle-import") (part "RESISTORRESISTOR/UPRIGHT/7.5"))
    )
    (comp (ref "R80")
      (value "10k")
      (footprint "eagle-import:RESISTOR_7.5")
      (libsource (lib "eagle-import") (part "RESISTORRESISTOR/UPRIGHT/7.5"))
    )
    (comp (ref "R81")
      (value "1k")
      (footprint "eagle-import:RESISTOR_7.5")
      (libsource (lib "eagle-import") (part "RESISTORRESISTOR/UPRIGHT/7.5"))
    )
    (comp (ref "R82")
      (value "1k")
      (footprint "eagle-import:RESISTOR_7.5")
      (libsource (lib "eagle-import") (part "RESISTORRESISTOR/UPRIGHT/7.5"))
    )
    (comp (ref "R83")
      (value "1k")
      (footprint "eagle-import:RESISTOR_7.5")
      (libsource (lib "eagle-import") (part "RESISTORRESISTOR/UPRIGHT/7.5"))
    )
  )
  (nets
    (net (code "1") (name "+3.3V") (class "Default")
      (node (ref "3.3V") (pin "1") (pinfunction "3_1") (pintype "passive"))
      (node (ref "3.3V1") (pin "1") (pinfunction "3_1") (pintype "passive"))
      (node (ref "IC6") (pin "9") (pinfunction "VDD_9") (pintype "power_in"))
      (node (ref "IC9") (pin "9") (pinfunction "VDD_9") (pintype "power_in"))
      (node (ref "R19") (pin "2") (pinfunction "2_2") (pintype "passive"))
      (node (ref "R24") (pin "2") (pinfunction "2_2") (pintype "passive"))
      (node (ref "R28") (pin "2") (pinfunction "2_2") (pintype "passive"))
      (node (ref "R32") (pin "2") (pinfunction "2_2") (pintype "passive"))
      (node (ref "R36") (pin "2") (pinfunction "2_2") (pintype "passive"))
      (node (ref "R40") (pin "2") (pinfunction "2_2") (pintype "passive"))
      (node (ref "R44") (pin "2") (pinfunction "2_2") (pintype "passive"))
      (node (ref "R48") (pin "2") (pinfunction "2_2") (pintype "passive"))
      (node (ref "R52") (pin "2") (pinfunction "2_2") (pintype "passive"))
      (node (ref "R56") (pin "2") (pinfunction "2_2") (pintype "passive"))
      (node (ref "R60") (pin "2") (pinfunction "2_2") (pintype "passive"))
      (node (ref "R64") (pin "2") (pinfunction "2_2") (pintype "passive"))
      (node (ref "R68") (pin "2") (pinfunction "2_2") (pintype "passive"))
      (node (ref "R72") (pin "2") (pinfunction "2_2") (pintype "passive"))
      (node (ref "R76") (pin "2") (pinfunction "2_2") (pintype "passive"))
      (node (ref "R80") (pin "2") (pinfunction "2_2") (pintype "passive"))
      (node (ref "R81") (pin "1") (pinfunction "1_1") (pintype "passive"))
      (node (ref "R82") (pin "1") (pinfunction "1_1") (pintype "passive"))
      (node (ref "R83") (pin "1") (pinfunction "1_1") (pintype "passive"))
    )
    (net (code "2") (name "GND") (class "Default")
      (node (ref "GND") (pin "1") (pinfunction "3_1") (pintype "passive"))
      (node (ref "GND2") (pin "1") (pinfunction "3_1") (pintype "passive"))
      (node (ref "GND3") (pin "1") (pinfunction "3_1") (pintype "passive"))
      (node (ref "IC6") (pin "10") (pinfunction "VSS_10") (pintype "power_in"))
      (node (ref "IC6") (pin "15") (pinfunction "A0_15") (pintype "input"))
      (node (ref "IC6") (pin "16") (pinfunction "A1_16") (pintype "input"))
      (node (ref "IC6") (pin "17") (pinfunction "A2_17") (pintype "input"))
      (node (ref "IC9") (pin "10") (pinfunction "VSS_10") (pintype "power_in"))
      (node (ref "IC9") (pin "16") (pinfunction "A1_16") (pintype "input"))
      (node (ref "IC9") (pin "17") (pinfunction "A2_17") (pintype "input"))
      (node (ref "Q1") (pin "3") (pinfunction "E_3") (pintype "passive"))
      (node (ref "Q10") (pin "3") (pinfunction "E_3") (pintype "passive"))
      (node (ref "Q11") (pin "3") (pinfunction "E_3") (pintype "passive"))
      (node (ref "Q12") (pin "3") (pinfunction "E_3") (pintype "passive"))
      (node (ref "Q13") (pin "3") (pinfunction "E_3") (pintype "passive"))
      (node (ref "Q14") (pin "3") (pinfunction "E_3") (pintype "passive"))
      (node (ref "Q15") (pin "3") (pinfunction "E_3") (pintype "passive"))
      (node (ref "Q16") (pin "3") (pinfunction "E_3") (pintype "passive"))
      (node (ref "Q2") (pin "3") (pinfunction "E_3") (pintype "passive"))
      (node (ref "Q3") (pin "3") (pinfunction "E_3") (pintype "passive"))
      (node (ref "Q4") (pin "3") (pinfunction "E_3") (pintype "passive"))
      (node (ref "Q5") (pin "3") (pinfunction "E_3") (pintype "passive"))
      (node (ref "Q6") (pin "3") (pinfunction "E_3") (pintype "passive"))
      (node (ref "Q7") (pin "3") (pinfunction "E_3") (pintype "passive"))
      (node (ref "Q8") (pin "3") (pinfunction "E_3") (pintype "passive"))
      (node (ref "Q9") (pin "3") (pinfunction "E_3") (pintype "passive"))
      (node (ref "R18") (pin "1") (pinfunction "1_1") (pintype "passive"))
      (node (ref "R23") (pin "1") (pinfunction "1_1") (pintype "passive"))
      (node (ref "R27") (pin "1") (pinfunction "1_1") (pintype "passive"))
      (node (ref "R31") (pin "1") (pinfunction "1_1") (pintype "passive"))
      (node (ref "R35") (pin "1") (pinfunction "1_1") (pintype "passive"))
      (node (ref "R39") (pin "1") (pinfunction "1_1") (pintype "passive"))
      (node (ref "R43") (pin "1") (pinfunction "1_1") (pintype "passive"))
      (node (ref "R47") (pin "1") (pinfunction "1_1") (pintype "passive"))
      (node (ref "R51") (pin "1") (pinfunction "1_1") (pintype "passive"))
      (node (ref "R55") (pin "1") (pinfunction "1_1") (pintype "passive"))
      (node (ref "R59") (pin "1") (pinfunction "1_1") (pintype "passive"))
      (node (ref "R63") (pin "1") (pinfunction "1_1") (pintype "passive"))
      (node (ref "R67") (pin "1") (pinfunction "1_1") (pintype "passive"))
      (node (ref "R71") (pin "1") (pinfunction "1_1") (pintype "passive"))
      (node (ref "R75") (pin "1") (pinfunction "1_1") (pintype "passive"))
      (node (ref "R79") (pin "1") (pinfunction "1_1") (pintype "passive"))
    )
    (net (code "3") (name "Net-(8_SCK-3)") (class "Default")
      (node (ref "8_SCK") (pin "1") (pinfunction "3_1") (pintype "passive"))
      (node (ref "IC6") (pin "12") (pinfunction "SCK_12") (pintype "input"))
      (node (ref "IC9") (pin "12") (pinfunction "SCK_12") (pintype "input"))
    )
    (net (code "4") (name "Net-(9_MISO-3)") (class "Default")
      (node (ref "9_MISO") (pin "1") (pinfunction "3_1") (pintype "passive"))
      (node (ref "IC6") (pin "14") (pinfunction "SO_14") (pintype "output"))
      (node (ref "IC9") (pin "14") (pinfunction "SO_14") (pintype "output"))
    )
    (net (code "5") (name "Net-(10_MOSI-3)") (class "Default")
      (node (ref "10_MOSI") (pin "1") (pinfunction "3_1") (pintype "passive"))
      (node (ref "IC6") (pin "13") (pinfunction "SI_13") (pintype "input"))
      (node (ref "IC9") (pin "13") (pinfunction "SI_13") (pintype "input"))
    )
    (net (code "6") (name "Net-(11-3)") (class "Default")
      (node (ref "11") (pin "1") (pinfunction "3_1") (pintype "passive"))
      (node (ref "IC6") (pin "11") (pinfunction "~{CS}_11") (pintype "input"))
    )
    (net (code "7") (name "Net-(12-3)") (class "Default")
      (node (ref "12") (pin "1") (pinfunction "3_1") (pintype "passive"))
      (node (ref "IC9") (pin "11") (pinfunction "~{CS}_11") (pintype "input"))
    )
    (net (code "8") (name "Net-(BTN1-3)") (class "Default")
      (node (ref "BTN1") (pin "1") (pinfunction "3_1") (pintype "passive"))
      (node (ref "GTIN1") (pin "1") (pinfunction "3_1") (pintype "passive"))
      (node (ref "R17") (pin "1") (pinfunction "1_1") (pintype "passive"))
    )
    (net (code "9") (name "Net-(BTN2-3)") (class "Default")
      (node (ref "BTN2") (pin "1") (pinfunction "3_1") (pintype "passive"))
      (node (ref "GTIN2") (pin "1") (pinfunction "3_1") (pintype "passive"))
      (node (ref "R22") (pin "1") (pinfunction "1_1") (pintype "passive"))
    )
    (net (code "10") (name "Net-(BTN3-3)") (class "Default")
      (node (ref "BTN3") (pin "1") (pinfunction "3_1") (pintype "passive"))
      (node (ref "GTIN3") (pin "1") (pinfunction "3_1") (pintype "passive"))
      (node (ref "R26") (pin "1") (pinfunction "1_1") (pintype "passive"))
    )
    (net (code "11") (name "Net-(BTN4-3)") (class "Default")
      (node (ref "BTN4") (pin "1") (pinfunction "3_1") (pintype "passive"))
      (node (ref "GTIN4") (pin "1") (pinfunction "3_1") (pintype "passive"))
      (node (ref "R30") (pin "1") (pinfunction "1_1") (pintype "passive"))
    )
    (net (code "12") (name "Net-(BTN5-3)") (class "Default")
      (node (ref "BTN5") (pin "1") (pinfunction "3_1") (pintype "passive"))
      (node (ref "GTIN5") (pin "1") (pinfunction "3_1") (pintype "passive"))
      (node (ref "R34") (pin "1") (pinfunction "1_1") (pintype "passive"))
    )
    (net (code "13") (name "Net-(BTN6-3)") (class "Default")
      (node (ref "BTN6") (pin "1") (pinfunction "3_1") (pintype "passive"))
      (node (ref "GTIN6") (pin "1") (pinfunction "3_1") (pintype "passive"))
      (node (ref "R38") (pin "1") (pinfunction "1_1") (pintype "passive"))
    )
    (net (code "14") (name "Net-(BTN7-3)") (class "Default")
      (node (ref "BTN7") (pin "1") (pinfunction "3_1") (pintype "passive"))
      (node (ref "GTIN7") (pin "1") (pinfunction "3_1") (pintype "passive"))
      (node (ref "R42") (pin "1") (pinfunction "1_1") (pintype "passive"))
    )
    (net (code "15") (name "Net-(BTN8-3)") (class "Default")
      (node (ref "BTN8") (pin "1") (pinfunction "3_1") (pintype "passive"))
      (node (ref "GTIN8") (pin "1") (pinfunction "3_1") (pintype "passive"))
      (node (ref "R46") (pin "1") (pinfunction "1_1") (pintype "passive"))
    )
    (net (code "16") (name "Net-(BTN9-3)") (class "Default")
      (node (ref "BTN9") (pin "1") (pinfunction "3_1") (pintype "passive"))
      (node (ref "GTIN9") (pin "1") (pinfunction "3_1") (pintype "passive"))
      (node (ref "R50") (pin "1") (pinfunction "1_1") (pintype "passive"))
    )
    (net (code "17") (name "Net-(BTN10-3)") (class "Default")
      (node (ref "BTN10") (pin "1") (pinfunction "3_1") (pintype "passive"))
      (node (ref "GTIN10") (pin "1") (pinfunction "3_1") (pintype "passive"))
      (node (ref "R54") (pin "1") (pinfunction "1_1") (pintype "passive"))
    )
    (net (code "18") (name "Net-(BTN11-3)") (class "Default")
      (node (ref "BTN11") (pin "1") (pinfunction "3_1") (pintype "passive"))
      (node (ref "GTIN11") (pin "1") (pinfunction "3_1") (pintype "passive"))
      (node (ref "R58") (pin "1") (pinfunction "1_1") (pintype "passive"))
    )
    (net (code "19") (name "Net-(BTN12-3)") (class "Default")
      (node (ref "BTN12") (pin "1") (pinfunction "3_1") (pintype "passive"))
      (node (ref "GTIN12") (pin "1") (pinfunction "3_1") (pintype "passive"))
      (node (ref "R62") (pin "1") (pinfunction "1_1") (pintype "passive"))
    )
    (net (code "20") (name "Net-(BTN13-3)") (class "Default")
      (node (ref "BTN13") (pin "1") (pinfunction "3_1") (pintype "passive"))
      (node (ref "GTIN13") (pin "1") (pinfunction "3_1") (pintype "passive"))
      (node (ref "R66") (pin "1") (pinfunction "1_1") (pintype "passive"))
    )
    (net (code "21") (name "Net-(BTN14-3)") (class "Default")
      (node (ref "BTN14") (pin "1") (pinfunction "3_1") (pintype "passive"))
      (node (ref "GTIN14") (pin "1") (pinfunction "3_1") (pintype "passive"))
      (node (ref "R70") (pin "1") (pinfunction "1_1") (pintype "passive"))
    )
    (net (code "22") (name "Net-(BTN15-3)") (class "Default")
      (node (ref "BTN15") (pin "1") (pinfunction "3_1") (pintype "passive"))
      (node (ref "GTIN15") (pin "1") (pinfunction "3_1") (pintype "passive"))
      (node (ref "R74") (pin "1") (pinfunction "1_1") (pintype "passive"))
    )
    (net (code "23") (name "Net-(BTN16-3)") (class "Default")
      (node (ref "BTN16") (pin "1") (pinfunction "3_1") (pintype "passive"))
      (node (ref "GTIN16") (pin "1") (pinfunction "3_1") (pintype "passive"))
      (node (ref "R78") (pin "1") (pinfunction "1_1") (pintype "passive"))
    )
    (net (code "24") (name "Net-(IC6-GPA0)") (class "Default")
      (node (ref "IC6") (pin "21") (pinfunction "GPA0_21") (pintype "bidirectional"))
      (node (ref "R1") (pin "1") (pinfunction "1_1") (pintype "passive"))
    )
    (net (code "25") (name "Net-(IC6-GPA1)") (class "Default")
      (node (ref "IC6") (pin "22") (pinfunction "GPA1_22") (pintype "bidirectional"))
      (node (ref "R2") (pin "1") (pinfunction "1_1") (pintype "passive"))
    )
    (net (code "26") (name "Net-(IC6-GPA2)") (class "Default")
      (node (ref "IC6") (pin "23") (pinfunction "GPA2_23") (pintype "bidirectional"))
      (node (ref "R3") (pin "1") (pinfunction "1_1") (pintype "passive"))
    )
    (net (code "27") (name "Net-(IC6-GPA3)") (class "Default")
      (node (ref "IC6") (pin "24") (pinfunction "GPA3_24") (pintype "bidirectional"))
      (node (ref "R4") (pin "1") (pinfunction "1_1") (pintype "passive"))
    )
    (net (code "28") (name "Net-(IC6-GPA4)") (class "Default")
      (node (ref "IC6") (pin "25") (pinfunction "GPA4_25") (pintype "bidirectional"))
      (node (ref "R5") (pin "1") (pinfunction "1_1") (pintype "passive"))
    )
    (net (code "29") (name "Net-(IC6-GPA5)") (class "Default")
      (node (ref "IC6") (pin "26") (pinfunction "GPA5_26") (pintype "bidirectional"))
      (node (ref "R6") (pin "1") (pinfunction "1_1") (pintype "passive"))
    )
    (net (code "30") (name "Net-(IC6-GPA6)") (class "Default")
      (node (ref "IC6") (pin "27") (pinfunction "GPA6_27") (pintype "bidirectional"))
      (node (ref "R7") (pin "1") (pinfunction "1_1") (pintype "passive"))
    )
    (net (code "31") (name "Net-(IC6-GPA7)") (class "Default")
      (node (ref "IC6") (pin "28") (pinfunction "GPA7_28") (pintype "bidirectional"))
      (node (ref "R8") (pin "1") (pinfunction "1_1") (pintype "passive"))
    )
    (net (code "32") (name "Net-(IC6-GPB0)") (class "Default")
      (node (ref "IC6") (pin "1") (pinfunction "GPB0_1") (pintype "bidirectional"))
      (node (ref "R9") (pin "1") (pinfunction "1_1") (pintype "passive"))
    )
    (net (code "33") (name "Net-(IC6-GPB1)") (class "Default")
      (node (ref "IC6") (pin "2") (pinfunction "GPB1_2") (pintype "bidirectional"))
      (node (ref "R10") (pin "1") (pinfunction "1_1") (pintype "passive"))
    )
    (net (code "34") (name "Net-(IC6-GPB2)") (class "Default")
      (node (ref "IC6") (pin "3") (pinfunction "GPB2_3") (pintype "bidirectional"))
      (node (ref "R11") (pin "1") (pinfunction "1_1") (pintype "passive"))
    )
    (net (code "35") (name "Net-(IC6-GPB3)") (class "Default")
      (node (ref "IC6") (pin "4") (pinfunction "GPB3_4") (pintype "bidirectional"))
      (node (ref "R12") (pin "1") (pinfunction "1_1") (pintype "passive"))
    )
    (net (code "36") (name "Net-(IC6-GPB4)") (class "Default")
      (node (ref "IC6") (pin "5") (pinfunction "GPB4_5") (pintype "bidirectional"))
      (node (ref "R13") (pin "1") (pinfunction "1_1") (pintype "passive"))
    )
    (net (code "37") (name "Net-(IC6-GPB5)") (class "Default")
      (node (ref "IC6") (pin "6") (pinfunction "GPB5_6") (pintype "bidirectional"))
      (node (ref "R14") (pin "1") (pinfunction "1_1") (pintype "passive"))
    )
    (net (code "38") (name "Net-(IC6-GPB6)") (class "Default")
      (node (ref "IC6") (pin "7") (pinfunction "GPB6_7") (pintype "bidirectional"))
      (node (ref "R15") (pin "1") (pinfunction "1_1") (pintype "passive"))
    )
    (net (code "39") (name "Net-(IC6-GPB7)") (class "Default")
      (node (ref "IC6") (pin "8") (pinfunction "GPB7_8") (pintype "bidirectional"))
      (node (ref "R16") (pin "1") (pinfunction "1_1") (pintype "passive"))
    )
    (net (code "40") (name "Net-(IC6-~{RESET})") (class "Default")
      (node (ref "IC6") (pin "18") (pinfunction "~{RESET}_18") (pintype "input"))
      (node (ref "R81") (pin "2") (pinfunction "2_2") (pintype "passive"))
    )
    (net (code "41") (name "Net-(IC9-A0)") (class "Default")
      (node (ref "IC9") (pin "15") (pinfunction "A0_15") (pintype "input"))
      (node (ref "R83") (pin "2") (pinfunction "2_2") (pintype "passive"))
    )
    (net (code "42") (name "Net-(IC9-GPA0)") (class "Default")
      (node (ref "IC9") (pin "21") (pinfunction "GPA0_21") (pintype "bidirectional"))
      (node (ref "R49") (pin "2") (pinfunction "2_2") (pintype "passive"))
    )
    (net (code "43") (name "Net-(IC9-GPA1)") (class "Default")
      (node (ref "IC9") (pin "22") (pinfunction "GPA1_22") (pintype "bidirectional"))
      (node (ref "R53") (pin "2") (pinfunction "2_2") (pintype "passive"))
    )
    (net (code "44") (name "Net-(IC9-GPA2)") (class "Default")
      (node (ref "IC9") (pin "23") (pinfunction "GPA2_23") (pintype "bidirectional"))
      (node (ref "R57") (pin "2") (pinfunction "2_2") (pintype "passive"))
    )
    (net (code "45") (name "Net-(IC9-GPA3)") (class "Default")
      (node (ref "IC9") (pin "24") (pinfunction "GPA3_24") (pintype "bidirectional"))
      (node (ref "R61") (pin "2") (pinfunction "2_2") (pintype "passive"))
    )
    (net (code "46") (name "Net-(IC9-GPA4)") (class "Default")
      (node (ref "IC9") (pin "25") (pinfunction "GPA4_25") (pintype "bidirectional"))
      (node (ref "R65") (pin "2") (pinfunction "2_2") (pintype "passive"))
    )
    (net (code "47") (name "Net-(IC9-GPA5)") (class "Default")
      (node (ref "IC9") (pin "26") (pinfunction "GPA5_26") (pintype "bidirectional"))
      (node (ref "R69") (pin "2") (pinfunction "2_2") (pintype "passive"))
    )
    (net (code "48") (name "Net-(IC9-GPA6)") (class "Default")
      (node (ref "IC9") (pin "27") (pinfunction "GPA6_27") (pintype "bidirectional"))
      (node (ref "R73") (pin "2") (pinfunction "2_2") (pintype "passive"))
    )
    (net (code "49") (name "Net-(IC9-GPA7)") (class "Default")
      (node (ref "IC9") (pin "28") (pinfunction "GPA7_28") (pintype "bidirectional"))
      (node (ref "R77") (pin "2") (pinfunction "2_2") (pintype "passive"))
    )
    (net (code "50") (name "Net-(IC9-GPB0)") (class "Default")
      (node (ref "IC9") (pin "1") (pinfunction "GPB0_1") (pintype "bidirectional"))
      (node (ref "R20") (pin "2") (pinfunction "2_2") (pintype "passive"))
    )
    (net (code "51") (name "Net-(IC9-GPB1)") (class "Default")
      (node (ref "IC9") (pin "2") (pinfunction "GPB1_2") (pintype "bidirectional"))
      (node (ref "R21") (pin "2") (pinfunction "2_2") (pintype "passive"))
    )
    (net (code "52") (name "Net-(IC9-GPB2)") (class "Default")
      (node (ref "IC9") (pin "3") (pinfunction "GPB2_3") (pintype "bidirectional"))
      (node (ref "R25") (pin "2") (pinfunction "2_2") (pintype "passive"))
    )
    (net (code "53") (name "Net-(IC9-GPB3)") (class "Default")
      (node (ref "IC9") (pin "4") (pinfunction "GPB3_4") (pintype "bidirectional"))
      (node (ref "R29") (pin "2") (pinfunction "2_2") (pintype "passive"))
    )
    (net (code "54") (name "Net-(IC9-GPB4)") (class "Default")
      (node (ref "IC9") (pin "5") (pinfunction "GPB4_5") (pintype "bidirectional"))
      (node (ref "R33") (pin "2") (pinfunction "2_2") (pintype "passive"))
    )
    (net (code "55") (name "Net-(IC9-GPB5)") (class "Default")
      (node (ref "IC9") (pin "6") (pinfunction "GPB5_6") (pintype "bidirectional"))
      (node (ref "R37") (pin "2") (pinfunction "2_2") (pintype "passive"))
    )
    (net (code "56") (name "Net-(IC9-GPB6)") (class "Default")
      (node (ref "IC9") (pin "7") (pinfunction "GPB6_7") (pintype "bidirectional"))
      (node (ref "R41") (pin "2") (pinfunction "2_2") (pintype "passive"))
    )
    (net (code "57") (name "Net-(IC9-GPB7)") (class "Default")
      (node (ref "IC9") (pin "8") (pinfunction "GPB7_8") (pintype "bidirectional"))
      (node (ref "R45") (pin "2") (pinfunction "2_2") (pintype "passive"))
    )
    (net (code "58") (name "Net-(IC9-~{RESET})") (class "Default")
      (node (ref "IC9") (pin "18") (pinfunction "~{RESET}_18") (pintype "input"))
      (node (ref "R82") (pin "2") (pinfunction "2_2") (pintype "passive"))
    )
    (net (code "59") (name "Net-(LED1-3)") (class "Default")
      (node (ref "LED1") (pin "1") (pinfunction "3_1") (pintype "passive"))
      (node (ref "R9") (pin "2") (pinfunction "2_2") (pintype "passive"))
    )
    (net (code "60") (name "Net-(LED2-3)") (class "Default")
      (node (ref "LED2") (pin "1") (pinfunction "3_1") (pintype "passive"))
      (node (ref "R10") (pin "2") (pinfunction "2_2") (pintype "passive"))
    )
    (net (code "61") (name "Net-(LED3-3)") (class "Default")
      (node (ref "LED3") (pin "1") (pinfunction "3_1") (pintype "passive"))
      (node (ref "R11") (pin "2") (pinfunction "2_2") (pintype "passive"))
    )
    (net (code "62") (name "Net-(LED4-3)") (class "Default")
      (node (ref "LED4") (pin "1") (pinfunction "3_1") (pintype "passive"))
      (node (ref "R12") (pin "2") (pinfunction "2_2") (pintype "passive"))
    )
    (net (code "63") (name "Net-(LED5-3)") (class "Default")
      (node (ref "LED5") (pin "1") (pinfunction "3_1") (pintype "passive"))
      (node (ref "R13") (pin "2") (pinfunction "2_2") (pintype "passive"))
    )
    (net (code "64") (name "Net-(LED6-3)") (class "Default")
      (node (ref "LED6") (pin "1") (pinfunction "3_1") (pintype "passive"))
      (node (ref "R14") (pin "2") (pinfunction "2_2") (pintype "passive"))
    )
    (net (code "65") (name "Net-(LED7-3)") (class "Default")
      (node (ref "LED7") (pin "1") (pinfunction "3_1") (pintype "passive"))
      (node (ref "R15") (pin "2") (pinfunction "2_2") (pintype "passive"))
    )
    (net (code "66") (name "Net-(LED8-3)") (class "Default")
      (node (ref "LED8") (pin "1") (pinfunction "3_1") (pintype "passive"))
      (node (ref "R16") (pin "2") (pinfunction "2_2") (pintype "passive"))
    )
    (net (code "67") (name "Net-(LED9-3)") (class "Default")
      (node (ref "LED9") (pin "1") (pinfunction "3_1") (pintype "passive"))
      (node (ref "R1") (pin "2") (pinfunction "2_2") (pintype "passive"))
    )
    (net (code "68") (name "Net-(LED10-3)") (class "Default")
      (node (ref "LED10") (pin "1") (pinfunction "3_1") (pintype "passive"))
      (node (ref "R2") (pin "2") (pinfunction "2_2") (pintype "passive"))
    )
    (net (code "69") (name "Net-(LED11-3)") (class "Default")
      (node (ref "LED11") (pin "1") (pinfunction "3_1") (pintype "passive"))
      (node (ref "R3") (pin "2") (pinfunction "2_2") (pintype "passive"))
    )
    (net (code "70") (name "Net-(LED12-3)") (class "Default")
      (node (ref "LED12") (pin "1") (pinfunction "3_1") (pintype "passive"))
      (node (ref "R4") (pin "2") (pinfunction "2_2") (pintype "passive"))
    )
    (net (code "71") (name "Net-(LED13-3)") (class "Default")
      (node (ref "LED13") (pin "1") (pinfunction "3_1") (pintype "passive"))
      (node (ref "R5") (pin "2") (pinfunction "2_2") (pintype "passive"))
    )
    (net (code "72") (name "Net-(LED14-3)") (class "Default")
      (node (ref "LED14") (pin "1") (pinfunction "3_1") (pintype "passive"))
      (node (ref "R6") (pin "2") (pinfunction "2_2") (pintype "passive"))
    )
    (net (code "73") (name "Net-(LED15-3)") (class "Default")
      (node (ref "LED15") (pin "1") (pinfunction "3_1") (pintype "passive"))
      (node (ref "R7") (pin "2") (pinfunction "2_2") (pintype "passive"))
    )
    (net (code "74") (name "Net-(LED16-3)") (class "Default")
      (node (ref "LED16") (pin "1") (pinfunction "3_1") (pintype "passive"))
      (node (ref "R8") (pin "2") (pinfunction "2_2") (pintype "passive"))
    )
    (net (code "75") (name "Net-(Q1-B)") (class "Default")
      (node (ref "Q1") (pin "2") (pinfunction "B_2") (pintype "passive"))
      (node (ref "R17") (pin "2") (pinfunction "2_2") (pintype "passive"))
      (node (ref "R18") (pin "2") (pinfunction "2_2") (pintype "passive"))
    )
    (net (code "76") (name "Net-(Q1-C)") (class "Default")
      (node (ref "Q1") (pin "1") (pinfunction "C_1") (pintype "passive"))
      (node (ref "R19") (pin "1") (pinfunction "1_1") (pintype "passive"))
      (node (ref "R20") (pin "1") (pinfunction "1_1") (pintype "passive"))
    )
    (net (code "77") (name "Net-(Q2-B)") (class "Default")
      (node (ref "Q2") (pin "2") (pinfunction "B_2") (pintype "passive"))
      (node (ref "R22") (pin "2") (pinfunction "2_2") (pintype "passive"))
      (node (ref "R23") (pin "2") (pinfunction "2_2") (pintype "passive"))
    )
    (net (code "78") (name "Net-(Q2-C)") (class "Default")
      (node (ref "Q2") (pin "1") (pinfunction "C_1") (pintype "passive"))
      (node (ref "R21") (pin "1") (pinfunction "1_1") (pintype "passive"))
      (node (ref "R24") (pin "1") (pinfunction "1_1") (pintype "passive"))
    )
    (net (code "79") (name "Net-(Q3-B)") (class "Default")
      (node (ref "Q3") (pin "2") (pinfunction "B_2") (pintype "passive"))
      (node (ref "R26") (pin "2") (pinfunction "2_2") (pintype "passive"))
      (node (ref "R27") (pin "2") (pinfunction "2_2") (pintype "passive"))
    )
    (net (code "80") (name "Net-(Q3-C)") (class "Default")
      (node (ref "Q3") (pin "1") (pinfunction "C_1") (pintype "passive"))
      (node (ref "R25") (pin "1") (pinfunction "1_1") (pintype "passive"))
      (node (ref "R28") (pin "1") (pinfunction "1_1") (pintype "passive"))
    )
    (net (code "81") (name "Net-(Q4-B)") (class "Default")
      (node (ref "Q4") (pin "2") (pinfunction "B_2") (pintype "passive"))
      (node (ref "R30") (pin "2") (pinfunction "2_2") (pintype "passive"))
      (node (ref "R31") (pin "2") (pinfunction "2_2") (pintype "passive"))
    )
    (net (code "82") (name "Net-(Q4-C)") (class "Default")
      (node (ref "Q4") (pin "1") (pinfunction "C_1") (pintype "passive"))
      (node (ref "R29") (pin "1") (pinfunction "1_1") (pintype "passive"))
      (node (ref "R32") (pin "1") (pinfunction "1_1") (pintype "passive"))
    )
    (net (code "83") (name "Net-(Q5-B)") (class "Default")
      (node (ref "Q5") (pin "2") (pinfunction "B_2") (pintype "passive"))
      (node (ref "R34") (pin "2") (pinfunction "2_2") (pintype "passive"))
      (node (ref "R35") (pin "2") (pinfunction "2_2") (pintype "passive"))
    )
    (net (code "84") (name "Net-(Q5-C)") (class "Default")
      (node (ref "Q5") (pin "1") (pinfunction "C_1") (pintype "passive"))
      (node (ref "R33") (pin "1") (pinfunction "1_1") (pintype "passive"))
      (node (ref "R36") (pin "1") (pinfunction "1_1") (pintype "passive"))
    )
    (net (code "85") (name "Net-(Q6-B)") (class "Default")
      (node (ref "Q6") (pin "2") (pinfunction "B_2") (pintype "passive"))
      (node (ref "R38") (pin "2") (pinfunction "2_2") (pintype "passive"))
      (node (ref "R39") (pin "2") (pinfunction "2_2") (pintype "passive"))
    )
    (net (code "86") (name "Net-(Q6-C)") (class "Default")
      (node (ref "Q6") (pin "1") (pinfunction "C_1") (pintype "passive"))
      (node (ref "R37") (pin "1") (pinfunction "1_1") (pintype "passive"))
      (node (ref "R40") (pin "1") (pinfunction "1_1") (pintype "passive"))
    )
    (net (code "87") (name "Net-(Q7-B)") (class "Default")
      (node (ref "Q7") (pin "2") (pinfunction "B_2") (pintype "passive"))
      (node (ref "R42") (pin "2") (pinfunction "2_2") (pintype "passive"))
      (node (ref "R43") (pin "2") (pinfunction "2_2") (pintype "passive"))
    )
    (net (code "88") (name "Net-(Q7-C)") (class "Default")
      (node (ref "Q7") (pin "1") (pinfunction "C_1") (pintype "passive"))
      (node (ref "R41") (pin "1") (pinfunction "1_1") (pintype "passive"))
      (node (ref "R44") (pin "1") (pinfunction "1_1") (pintype "passive"))
    )
    (net (code "89") (name "Net-(Q8-B)") (class "Default")
      (node (ref "Q8") (pin "2") (pinfunction "B_2") (pintype "passive"))
      (node (ref "R46") (pin "2") (pinfunction "2_2") (pintype "passive"))
      (node (ref "R47") (pin "2") (pinfunction "2_2") (pintype "passive"))
    )
    (net (code "90") (name "Net-(Q8-C)") (class "Default")
      (node (ref "Q8") (pin "1") (pinfunction "C_1") (pintype "passive"))
      (node (ref "R45") (pin "1") (pinfunction "1_1") (pintype "passive"))
      (node (ref "R48") (pin "1") (pinfunction "1_1") (pintype "passive"))
    )
    (net (code "91") (name "Net-(Q9-B)") (class "Default")
      (node (ref "Q9") (pin "2") (pinfunction "B_2") (pintype "passive"))
      (node (ref "R50") (pin "2") (pinfunction "2_2") (pintype "passive"))
      (node (ref "R51") (pin "2") (pinfunction "2_2") (pintype "passive"))
    )
    (net (code "92") (name "Net-(Q9-C)") (class "Default")
      (node (ref "Q9") (pin "1") (pinfunction "C_1") (pintype "passive"))
      (node (ref "R49") (pin "1") (pinfunction "1_1") (pintype "passive"))
      (node (ref "R52") (pin "1") (pinfunction "1_1") (pintype "passive"))
    )
    (net (code "93") (name "Net-(Q10-B)") (class "Default")
      (node (ref "Q10") (pin "2") (pinfunction "B_2") (pintype "passive"))
      (node (ref "R54") (pin "2") (pinfunction "2_2") (pintype "passive"))
      (node (ref "R55") (pin "2") (pinfunction "2_2") (pintype "passive"))
    )
    (net (code "94") (name "Net-(Q10-C)") (class "Default")
      (node (ref "Q10") (pin "1") (pinfunction "C_1") (pintype "passive"))
      (node (ref "R53") (pin "1") (pinfunction "1_1") (pintype "passive"))
      (node (ref "R56") (pin "1") (pinfunction "1_1") (pintype "passive"))
    )
    (net (code "95") (name "Net-(Q11-B)") (class "Default")
      (node (ref "Q11") (pin "2") (pinfunction "B_2") (pintype "passive"))
      (node (ref "R58") (pin "2") (pinfunction "2_2") (pintype "passive"))
      (node (ref "R59") (pin "2") (pinfunction "2_2") (pintype "passive"))
    )
    (net (code "96") (name "Net-(Q11-C)") (class "Default")
      (node (ref "Q11") (pin "1") (pinfunction "C_1") (pintype "passive"))
      (node (ref "R57") (pin "1") (pinfunction "1_1") (pintype "passive"))
      (node (ref "R60") (pin "1") (pinfunction "1_1") (pintype "passive"))
    )
    (net (code "97") (name "Net-(Q12-B)") (class "Default")
      (node (ref "Q12") (pin "2") (pinfunction "B_2") (pintype "passive"))
      (node (ref "R62") (pin "2") (pinfunction "2_2") (pintype "passive"))
      (node (ref "R63") (pin "2") (pinfunction "2_2") (pintype "passive"))
    )
    (net (code "98") (name "Net-(Q12-C)") (class "Default")
      (node (ref "Q12") (pin "1") (pinfunction "C_1") (pintype "passive"))
      (node (ref "R61") (pin "1") (pinfunction "1_1") (pintype "passive"))
      (node (ref "R64") (pin "1") (pinfunction "1_1") (pintype "passive"))
    )
    (net (code "99") (name "Net-(Q13-B)") (class "Default")
      (node (ref "Q13") (pin "2") (pinfunction "B_2") (pintype "passive"))
      (node (ref "R66") (pin "2") (pinfunction "2_2") (pintype "passive"))
      (node (ref "R67") (pin "2") (pinfunction "2_2") (pintype "passive"))
    )
    (net (code "100") (name "Net-(Q13-C)") (class "Default")
      (node (ref "Q13") (pin "1") (pinfunction "C_1") (pintype "passive"))
      (node (ref "R65") (pin "1") (pinfunction "1_1") (pintype "passive"))
      (node (ref "R68") (pin "1") (pinfunction "1_1") (pintype "passive"))
    )
    (net (code "101") (name "Net-(Q14-B)") (class "Default")
      (node (ref "Q14") (pin "2") (pinfunction "B_2") (pintype "passive"))
      (node (ref "R70") (pin "2") (pinfunction "2_2") (pintype "passive"))
      (node (ref "R71") (pin "2") (pinfunction "2_2") (pintype "passive"))
    )
    (net (code "102") (name "Net-(Q14-C)") (class "Default")
      (node (ref "Q14") (pin "1") (pinfunction "C_1") (pintype "passive"))
      (node (ref "R69") (pin "1") (pinfunction "1_1") (pintype "passive"))
      (node (ref "R72") (pin "1") (pinfunction "1_1") (pintype "passive"))
    )
    (net (code "103") (name "Net-(Q15-B)") (class "Default")
      (node (ref "Q15") (pin "2") (pinfunction "B_2") (pintype "passive"))
      (node (ref "R74") (pin "2") (pinfunction "2_2") (pintype "passive"))
      (node (ref "R75") (pin "2") (pinfunction "2_2") (pintype "passive"))
    )
    (net (code "104") (name "Net-(Q15-C)") (class "Default")
      (node (ref "Q15") (pin "1") (pinfunction "C_1") (pintype "passive"))
      (node (ref "R73") (pin "1") (pinfunction "1_1") (pintype "passive"))
      (node (ref "R76") (pin "1") (pinfunction "1_1") (pintype "passive"))
    )
    (net (code "105") (name "Net-(Q16-B)") (class "Default")
      (node (ref "Q16") (pin "2") (pinfunction "B_2") (pintype "passive"))
      (node (ref "R78") (pin "2") (pinfunction "2_2") (pintype "passive"))
      (node (ref "R79") (pin "2") (pinfunction "2_2") (pintype "passive"))
    )
    (net (code "106") (name "Net-(Q16-C)") (class "Default")
      (node (ref "Q16") (pin "1") (pinfunction "C_1") (pintype "passive"))
      (node (ref "R77") (pin "1") (pinfunction "1_1") (pintype "passive"))
      (node (ref "R80") (pin "1") (pinfunction "1_1") (pintype "passive"))
    )
    (net (code "107") (name "unconnected-(0-3-Pad1)") (class "Default")
      (node (ref "0") (pin "1") (pinfunction "3_1") (pintype "passive"))
    )
    (net (code "108") (name "unconnected-(1_SD_D3-3-Pad1)") (class "Default")
      (node (ref "1_SD_D3") (pin "1") (pinfunction "3_1") (pintype "passive"))
    )
    (net (code "109") (name "unconnected-(2_SD_D2-3-Pad1)") (class "Default")
      (node (ref "2_SD_D2") (pin "1") (pinfunction "3_1") (pintype "passive"))
    )
    (net (code "110") (name "unconnected-(3_SD_D1-3-Pad1)") (class "Default")
      (node (ref "3_SD_D1") (pin "1") (pinfunction "3_1") (pintype "passive"))
    )
    (net (code "111") (name "unconnected-(4_SD_D0-3-Pad1)") (class "Default")
      (node (ref "4_SD_D0") (pin "1") (pinfunction "3_1") (pintype "passive"))
    )
    (net (code "112") (name "unconnected-(5V-3-Pad1)") (class "Default")
      (node (ref "5V") (pin "1") (pinfunction "3_1") (pintype "passive"))
    )
    (net (code "113") (name "unconnected-(5_SD_CMD-3-Pad1)") (class "Default")
      (node (ref "5_SD_CMD") (pin "1") (pinfunction "3_1") (pintype "passive"))
    )
    (net (code "114") (name "unconnected-(6_SD_CLK-3-Pad1)") (class "Default")
      (node (ref "6_SD_CLK") (pin "1") (pinfunction "3_1") (pintype "passive"))
    )
    (net (code "115") (name "unconnected-(7_CS-3-Pad1)") (class "Default")
      (node (ref "7_CS") (pin "1") (pinfunction "3_1") (pintype "passive"))
    )
    (net (code "116") (name "unconnected-(13_TX-3-Pad1)") (class "Default")
      (node (ref "13_TX") (pin "1") (pinfunction "3_1") (pintype "passive"))
    )
    (net (code "117") (name "unconnected-(14_RX-3-Pad1)") (class "Default")
      (node (ref "14_RX") (pin "1") (pinfunction "3_1") (pintype "passive"))
    )
    (net (code "118") (name "unconnected-(29-3-Pad1)") (class "Default")
      (node (ref "29") (pin "1") (pinfunction "3_1") (pintype "passive"))
    )
    (net (code "119") (name "unconnected-(30-3-Pad1)") (class "Default")
      (node (ref "30") (pin "1") (pinfunction "3_1") (pintype "passive"))
    )
    (net (code "120") (name "unconnected-(IC6-INTA-Pad20)") (class "Default")
      (node (ref "IC6") (pin "20") (pinfunction "INTA_20") (pintype "output"))
    )
    (net (code "121") (name "unconnected-(IC6-INTB-Pad19)") (class "Default")
      (node (ref "IC6") (pin "19") (pinfunction "INTB_19") (pintype "output"))
    )
    (net (code "122") (name "unconnected-(IC9-INTA-Pad20)") (class "Default")
      (node (ref "IC9") (pin "20") (pinfunction "INTA_20") (pintype "output"))
    )
    (net (code "123") (name "unconnected-(IC9-INTB-Pad19)") (class "Default")
      (node (ref "IC9") (pin "19") (pinfunction "INTB_19") (pintype "output"))
    )
  )
)
